# Fan_Power_Switch.net
KiCad netlist of a schematic drawn in Altium Designer
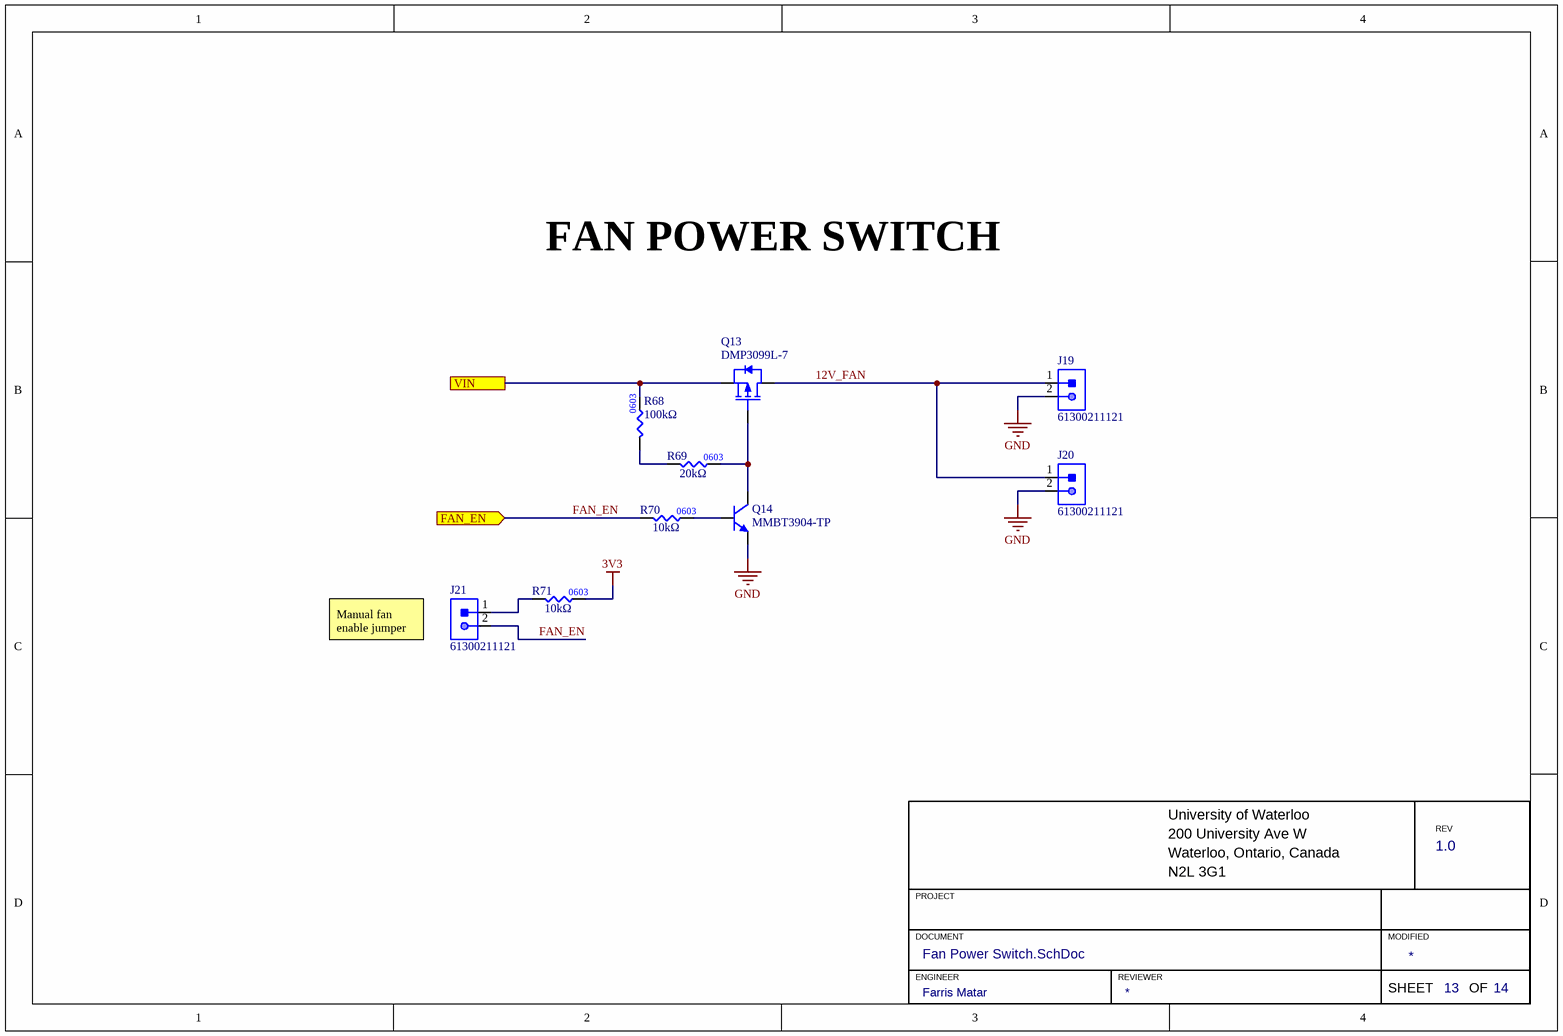
[diagram p0: Fan Power Switch.SchDoc]

(export (version "E")
  (design (tool "Eeschema 10.0.6"))
  (components
    (comp (ref "J19")
      (value "HEADER 2x1")
      (footprint "HDR1X2")
      (description "HEADER 2X1")
      (fields (field (name "MANUFACTURER PART NUMBER 1") "61300211121"))
      (libsource (lib "Personal_Schematic_Library_2022") (part "HEADER 2x1"))
    )
    (comp (ref "J20")
      (value "HEADER 2x1")
      (footprint "HDR1X2")
      (description "HEADER 2X1")
      (fields (field (name "MANUFACTURER PART NUMBER 1") "61300211121"))
      (libsource (lib "Personal_Schematic_Library_2022") (part "HEADER 2x1"))
    )
    (comp (ref "J21")
      (value "HEADER 2x1")
      (footprint "HDR1X2")
      (description "HEADER 2X1")
      (fields (field (name "MANUFACTURER PART NUMBER 1") "61300211121"))
      (libsource (lib "") (part "HEADER 2x1_1"))
    )
    (comp (ref "Q13")
      (value "PMOS_30V_3.8A")
      (footprint "DIO-INC_SOT23")
      (description "MOSFET P-CH 30V 3.8A SOT23")
      (fields (field (name "MANUFACTURER PART NUMBER 1") "DMP3099L-7"))
      (libsource (lib "Personal_Schematic_Library_2022") (part "PMOS_30V_3.8A"))
    )
    (comp (ref "Q14")
      (value "NPN_40V_100mA")
      (footprint "SOT23-3")
      (description "TRANS NPN 40V 0.2A SOT23")
      (fields (field (name "MANUFACTURER PART NUMBER 1") "MMBT3904-TP"))
      (libsource (lib "Personal_Schematic_Library_2022") (part "NPN_40V_100mA"))
    )
    (comp (ref "R68")
      (value "100kΩ")
      (footprint "RES0603")
      (description "RES 100K OHM 1% 1/10W 0603")
      (fields (field (name "Comment") "RES_100kΩ_0603_1%"))
      (libsource (lib "Personal_Schematic_Library_2022") (part "RES_100kΩ_0603_1%"))
    )
    (comp (ref "R69")
      (value "20kΩ")
      (footprint "RES0603")
      (description "RES 20K OHM 1% 1/10W 0603")
      (fields (field (name "Comment") "RES_20kΩ_0603_1%"))
      (libsource (lib "Personal_Schematic_Library_2022") (part "RES_20kΩ_0603_1%"))
    )
    (comp (ref "R70")
      (value "10kΩ")
      (footprint "RES0603")
      (description "RES 10K OHM 1% 1/8W 0603")
      (fields (field (name "Comment") "RES_10kΩ_0603_1%"))
      (libsource (lib "Personal_Schematic_Library_2022") (part "RES_10kΩ_0603_1%"))
    )
    (comp (ref "R71")
      (value "10kΩ")
      (footprint "RES0603")
      (description "RES 10K OHM 1% 1/8W 0603")
      (fields (field (name "Comment") "RES_10kΩ_0603_1%"))
      (libsource (lib "Personal_Schematic_Library_2022") (part "RES_10kΩ_0603_1%"))
    )
  )
  (nets
    (net (code "1") (name "/12V_FAN") (class "Default")
      (node (ref "J19") (pin "1") (pinfunction "VCC_1") (pintype "passive"))
      (node (ref "J20") (pin "1") (pinfunction "VCC_1") (pintype "passive"))
      (node (ref "Q13") (pin "3") (pinfunction "Drain_3") (pintype "passive"))
    )
    (net (code "2") (name "/FAN_EN") (class "Default")
      (node (ref "J21") (pin "2") (pinfunction "2_2") (pintype "passive"))
      (node (ref "R70") (pin "1") (pinfunction "1_1") (pintype "passive"))
    )
    (net (code "3") (name "/VIN") (class "Default")
      (node (ref "Q13") (pin "2") (pinfunction "Source_2") (pintype "passive"))
      (node (ref "R68") (pin "2") (pinfunction "2_2") (pintype "passive"))
    )
    (net (code "4") (name "3V3") (class "Default")
      (node (ref "R71") (pin "2") (pinfunction "2_2") (pintype "passive"))
    )
    (net (code "5") (name "GND") (class "Default")
      (node (ref "J19") (pin "2") (pinfunction "2_2") (pintype "passive"))
      (node (ref "J20") (pin "2") (pinfunction "2_2") (pintype "passive"))
      (node (ref "Q14") (pin "2") (pinfunction "E_2") (pintype "passive"))
    )
    (net (code "6") (name "Net-(J21-VCC)") (class "Default")
      (node (ref "J21") (pin "1") (pinfunction "VCC_1") (pintype "passive"))
      (node (ref "R71") (pin "1") (pinfunction "1_1") (pintype "passive"))
    )
    (net (code "7") (name "Net-(Q13-Gate)") (class "Default")
      (node (ref "Q13") (pin "1") (pinfunction "Gate_1") (pintype "passive"))
      (node (ref "Q14") (pin "3") (pinfunction "C_3") (pintype "passive"))
      (node (ref "R69") (pin "2") (pinfunction "2_2") (pintype "passive"))
    )
    (net (code "8") (name "Net-(Q14-B)") (class "Default")
      (node (ref "Q14") (pin "1") (pinfunction "B_1") (pintype "passive"))
      (node (ref "R70") (pin "2") (pinfunction "2_2") (pintype "passive"))
    )
    (net (code "9") (name "Net-(R68-Pad1)") (class "Default")
      (node (ref "R68") (pin "1") (pinfunction "1_1") (pintype "passive"))
      (node (ref "R69") (pin "1") (pinfunction "1_1") (pintype "passive"))
    )
  )
)
